# minimal-atmega328p-arduino.net
KiCad netlist of a schematic drawn in EAGLE
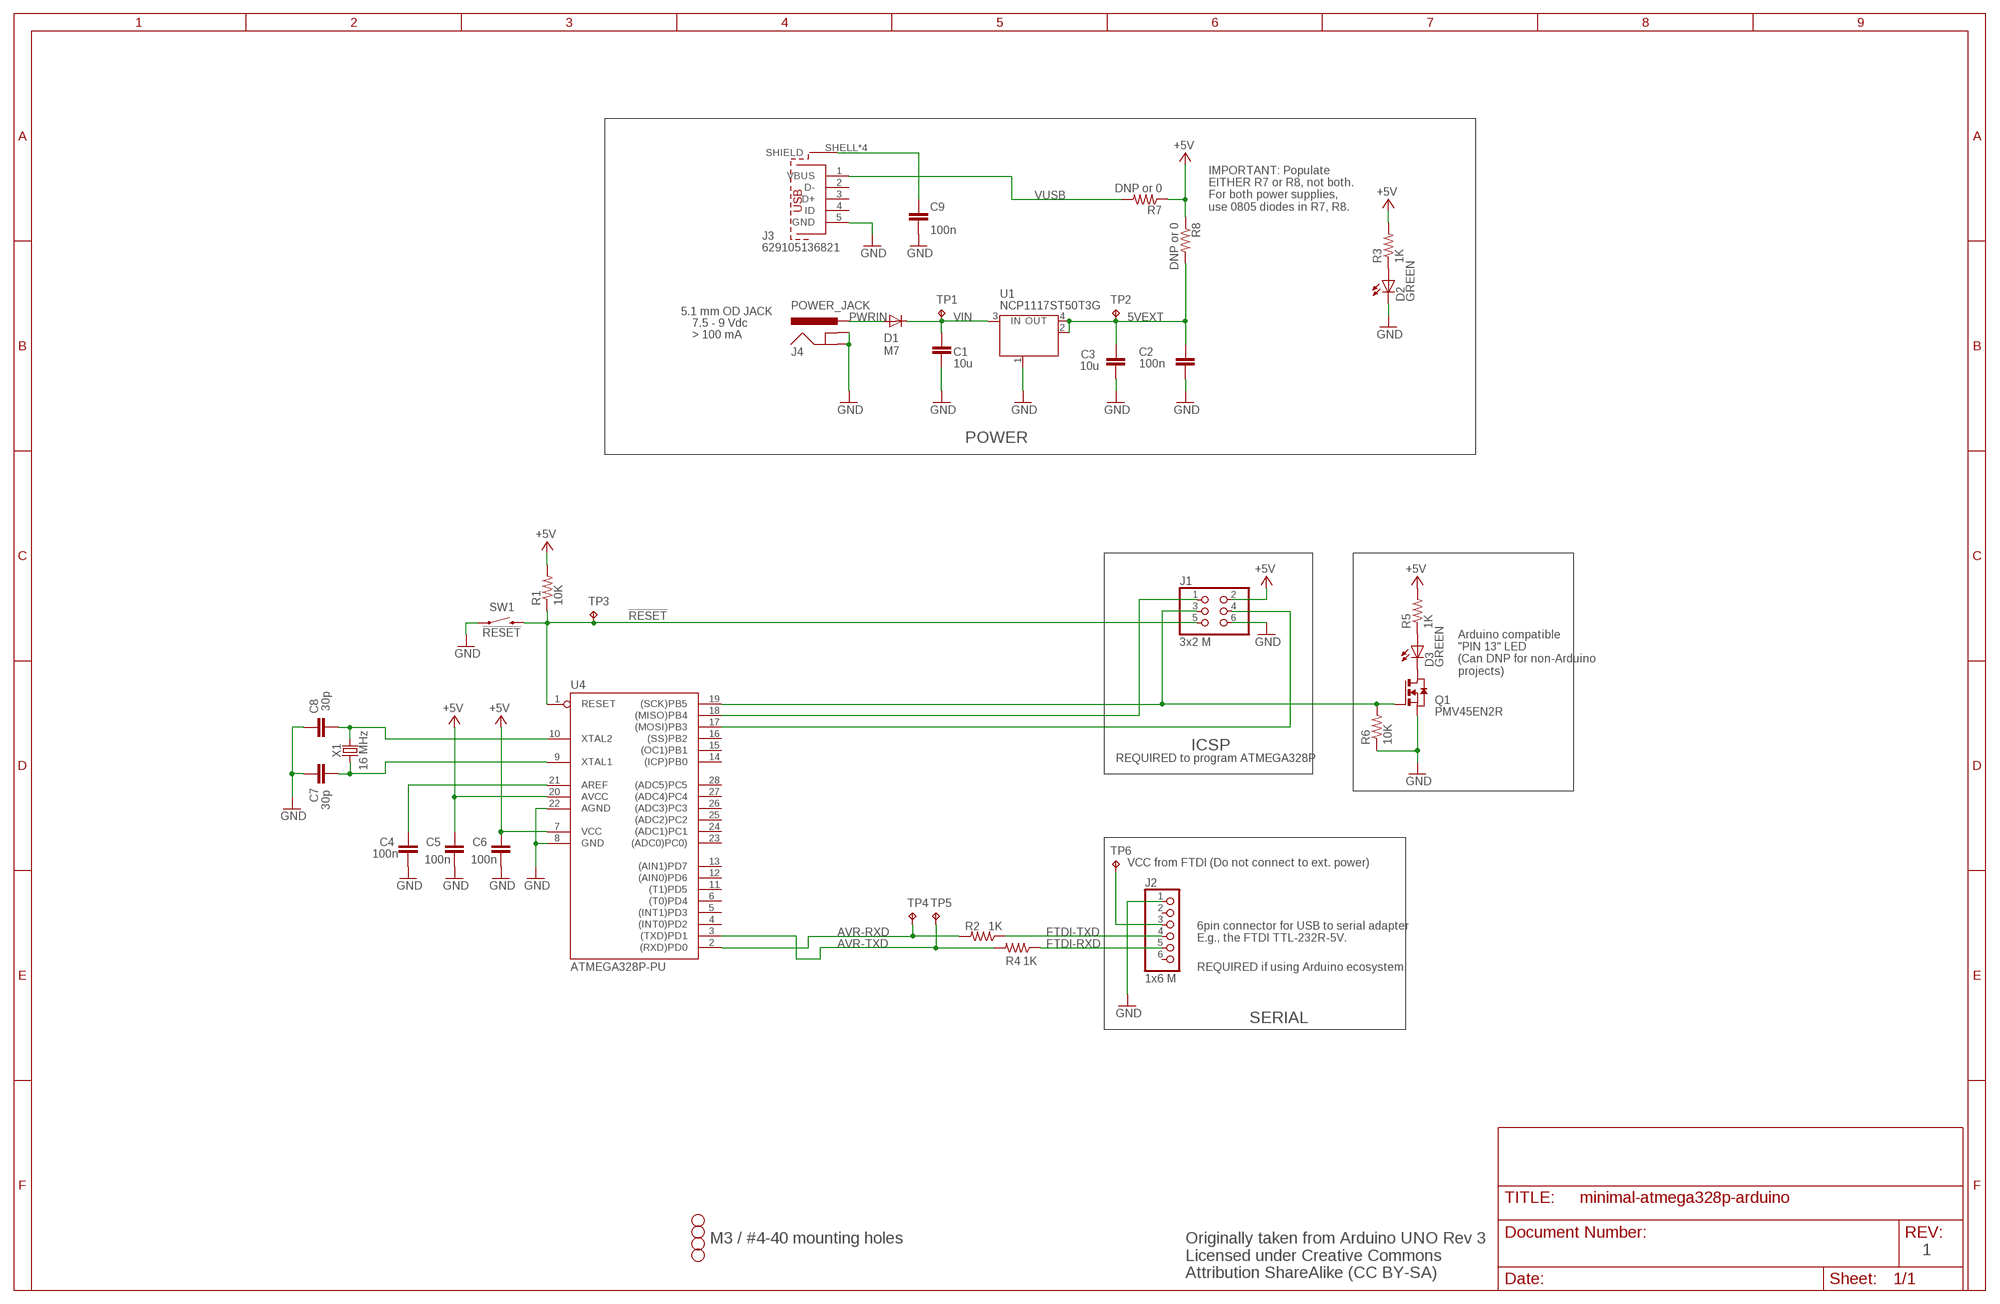
[diagram p0: schematic, sheet 1]

(export (version "E")
  (design (tool "Eeschema 10.0.6"))
  (components
    (comp (ref "C1")
      (value "10u")
      (footprint "eagle-import:C0805K")
      (fields (field (name "MFR") "Samsung") (field (name "MPN") "CL21A106KOQNNNG"))
      (libsource (lib "eagle-import") (part "C-EUC0805K"))
    )
    (comp (ref "C2")
      (value "100n")
      (footprint "eagle-import:C0805K")
      (fields (field (name "MFR") "Samsung") (field (name "MPN") "CL21B104KBCNNNC"))
      (libsource (lib "eagle-import") (part "C-EUC0805K"))
    )
    (comp (ref "C3")
      (value "10u")
      (footprint "eagle-import:C0805K")
      (fields (field (name "MFR") "Samsung") (field (name "MPN") "CL21A106KOQNNNG"))
      (libsource (lib "eagle-import") (part "C-EUC0805K"))
    )
    (comp (ref "C4")
      (value "100n")
      (footprint "eagle-import:C0805K")
      (fields (field (name "MFR") "Samsung") (field (name "MPN") "CL21B104KBCNNNC"))
      (libsource (lib "eagle-import") (part "C-EUC0805K"))
    )
    (comp (ref "C5")
      (value "100n")
      (footprint "eagle-import:C0805K")
      (fields (field (name "MFR") "Samsung") (field (name "MPN") "CL21B104KBCNNNC"))
      (libsource (lib "eagle-import") (part "C-EUC0805K"))
    )
    (comp (ref "C6")
      (value "100n")
      (footprint "eagle-import:C0805K")
      (fields (field (name "MFR") "Samsung") (field (name "MPN") "CL21B104KBCNNNC"))
      (libsource (lib "eagle-import") (part "C-EUC0805K"))
    )
    (comp (ref "C7")
      (value "30p")
      (footprint "eagle-import:C0805K")
      (fields (field (name "MFR") "Samsung") (field (name "MPN") "CL21C180JBANNNC"))
      (libsource (lib "eagle-import") (part "C-EUC0805K"))
    )
    (comp (ref "C8")
      (value "30p")
      (footprint "eagle-import:C0805K")
      (fields (field (name "MFR") "Samsung") (field (name "MPN") "CL21C300JBANNNC"))
      (libsource (lib "eagle-import") (part "C-EUC0805K"))
    )
    (comp (ref "C9")
      (value "100n")
      (footprint "eagle-import:C0805K")
      (fields (field (name "MFR") "Samsung") (field (name "MPN") "CL21B104KBCNNNC"))
      (libsource (lib "eagle-import") (part "C-EUC0805K"))
    )
    (comp (ref "D1")
      (value "M7")
      (footprint "eagle-import:SMB")
      (fields (field (name "MFR") "SMC Diode") (field (name "MPN") "10BQ030TR"))
      (libsource (lib "eagle-import") (part "DIODE-SMB"))
    )
    (comp (ref "D2")
      (value "GREEN")
      (footprint "eagle-import:CHIP-LED0805")
      (fields (field (name "MFR") "Würth Elektronik") (field (name "MPN") "150080GS75000"))
      (libsource (lib "eagle-import") (part "LEDCHIP-LED0805"))
    )
    (comp (ref "D3")
      (value "GREEN")
      (footprint "eagle-import:CHIP-LED0805")
      (fields (field (name "MFR") "Würth Elektronik") (field (name "MPN") "150080GS75000"))
      (libsource (lib "eagle-import") (part "LEDCHIP-LED0805"))
    )
    (comp (ref "H1")
      (value "STAND-OFF")
      (footprint "eagle-import:STAND-OFF")
      (libsource (lib "eagle-import") (part "STAND-OFF"))
    )
    (comp (ref "H2")
      (value "STAND-OFF")
      (footprint "eagle-import:STAND-OFF")
      (libsource (lib "eagle-import") (part "STAND-OFF"))
    )
    (comp (ref "H3")
      (value "STAND-OFF")
      (footprint "eagle-import:STAND-OFF")
      (libsource (lib "eagle-import") (part "STAND-OFF"))
    )
    (comp (ref "H4")
      (value "STAND-OFF")
      (footprint "eagle-import:STAND-OFF")
      (libsource (lib "eagle-import") (part "STAND-OFF"))
    )
    (comp (ref "J1")
      (value "3x2 M")
      (footprint "eagle-import:2X03")
      (fields (field (name "MFR") "Harwin") (field (name "MPN") "M20-9980345"))
      (libsource (lib "eagle-import") (part "PINHD-2X3"))
    )
    (comp (ref "J2")
      (value "1x6 M")
      (footprint "eagle-import:1X06")
      (fields (field (name "MFR") "Sullins") (field (name "MPN") "PRPC006SAAN-RC"))
      (libsource (lib "eagle-import") (part "PINHD-1X6"))
    )
    (comp (ref "J3")
      (value "629105136821")
      (footprint "eagle-import:629105136821")
      (fields (field (name "MFR") "Wurth"))
      (libsource (lib "eagle-import") (part "629105136821"))
    )
    (comp (ref "J4")
      (value "POWER_JACK")
      (footprint "eagle-import:POWER_JACK_PTH")
      (fields (field (name "MFR") "CUI") (field (name "MPN") "PJ-202A"))
      (libsource (lib "eagle-import") (part "POWER_JACK"))
    )
    (comp (ref "Q1")
      (value "PMV45EN2R")
      (footprint "eagle-import:SOT-23")
      (fields (field (name "MFR") "Nexperia") (field (name "MPN") "PMV45EN2R"))
      (libsource (lib "eagle-import") (part "NMOSSOT23"))
    )
    (comp (ref "R1")
      (value "10K")
      (footprint "eagle-import:R0805")
      (fields (field (name "MFR") "Yageo") (field (name "MPN") "RC0805FR-0710KL"))
      (libsource (lib "eagle-import") (part "R-US_R0805"))
    )
    (comp (ref "R2")
      (value "1K")
      (footprint "eagle-import:R0805")
      (fields (field (name "MFR") "Yageo") (field (name "MPN") "RC0805FR-071KL"))
      (libsource (lib "eagle-import") (part "R-US_R0805"))
    )
    (comp (ref "R3")
      (value "1K")
      (footprint "eagle-import:R0805")
      (fields (field (name "MFR") "Yageo") (field (name "MPN") "RC0805FR-071KL"))
      (libsource (lib "eagle-import") (part "R-US_R0805"))
    )
    (comp (ref "R4")
      (value "1K")
      (footprint "eagle-import:R0805")
      (fields (field (name "MFR") "Yageo") (field (name "MPN") "RC0805FR-071KL"))
      (libsource (lib "eagle-import") (part "R-US_R0805"))
    )
    (comp (ref "R5")
      (value "1K")
      (footprint "eagle-import:R0805")
      (fields (field (name "MFR") "Yageo") (field (name "MPN") "RC0805FR-071KL"))
      (libsource (lib "eagle-import") (part "R-US_R0805"))
    )
    (comp (ref "R6")
      (value "10K")
      (footprint "eagle-import:R0805")
      (fields (field (name "MFR") "Yageo") (field (name "MPN") "RC0805FR-0710KL"))
      (libsource (lib "eagle-import") (part "R-US_R0805"))
    )
    (comp (ref "R7")
      (value "DNP or 0")
      (footprint "eagle-import:R0805")
      (fields (field (name "MFR") "Yageo") (field (name "MPN") "RC0805JR-070RL"))
      (libsource (lib "eagle-import") (part "R-US_R0805"))
    )
    (comp (ref "R8")
      (value "DNP or 0")
      (footprint "eagle-import:R0805")
      (fields (field (name "MFR") "Yageo") (field (name "MPN") "RC0805JR-070RL"))
      (libsource (lib "eagle-import") (part "R-US_R0805"))
    )
    (comp (ref "SW1")
      (value "!RESET")
      (footprint "eagle-import:TACTILE_SWITCH_SMD")
      (fields (field (name "MFR") "C&K") (field (name "MPN") "RS-187R05A2-DS MT RT"))
      (libsource (lib "eagle-import") (part "SWITCH-MOMENTARY-2SMD"))
    )
    (comp (ref "TP1")
      (value "TPPAD1-13")
      (footprint "eagle-import:P1-13")
      (libsource (lib "eagle-import") (part "TPPAD1-13"))
    )
    (comp (ref "TP2")
      (value "TPPAD1-13")
      (footprint "eagle-import:P1-13")
      (libsource (lib "eagle-import") (part "TPPAD1-13"))
    )
    (comp (ref "TP3")
      (value "TPPAD1-13")
      (footprint "eagle-import:P1-13")
      (libsource (lib "eagle-import") (part "TPPAD1-13"))
    )
    (comp (ref "TP4")
      (value "TPPAD1-13")
      (footprint "eagle-import:P1-13")
      (libsource (lib "eagle-import") (part "TPPAD1-13"))
    )
    (comp (ref "TP5")
      (value "TPPAD1-13")
      (footprint "eagle-import:P1-13")
      (libsource (lib "eagle-import") (part "TPPAD1-13"))
    )
    (comp (ref "TP6")
      (value "TPPAD1-13")
      (footprint "eagle-import:P1-13")
      (libsource (lib "eagle-import") (part "TPPAD1-13"))
    )
    (comp (ref "U1")
      (value "NCP1117ST50T3G")
      (footprint "eagle-import:SOT223")
      (fields (field (name "MFR") "ON Semiconductor"))
      (libsource (lib "eagle-import") (part "MC33269ST-3.3T3"))
    )
    (comp (ref "U4")
      (value "ATMEGA328P-PU")
      (footprint "eagle-import:DIL28-3")
      (fields (field (name "MFR") "Microchip"))
      (libsource (lib "eagle-import") (part "ATMEGA328P-PU"))
    )
    (comp (ref "X1")
      (value "16 MHz")
      (footprint "eagle-import:HC49UP")
      (fields (field (name "MFR") "ECS") (field (name "MPN") "ECS-160-18-5PX-TR"))
      (libsource (lib "eagle-import") (part "CRYSTALSMD-HC49UP"))
    )
  )
  (nets
    (net (code "1") (name "+5V") (class "Default")
      (node (ref "C5") (pin "2") (pinfunction "2_2") (pintype "passive"))
      (node (ref "C6") (pin "2") (pinfunction "2_2") (pintype "passive"))
      (node (ref "J1") (pin "2") (pinfunction "2_2") (pintype "passive"))
      (node (ref "R1") (pin "2") (pinfunction "2_2") (pintype "passive"))
      (node (ref "R3") (pin "2") (pinfunction "2_2") (pintype "passive"))
      (node (ref "R5") (pin "2") (pinfunction "2_2") (pintype "passive"))
      (node (ref "R7") (pin "1") (pinfunction "1_1") (pintype "passive"))
      (node (ref "R8") (pin "1") (pinfunction "1_1") (pintype "passive"))
      (node (ref "U4") (pin "20") (pinfunction "AVCC_20") (pintype "power_in"))
      (node (ref "U4") (pin "7") (pinfunction "VCC_7") (pintype "power_in"))
    )
    (net (code "2") (name "/5VEXT") (class "Default")
      (node (ref "C2") (pin "2") (pinfunction "2_2") (pintype "passive"))
      (node (ref "C3") (pin "1") (pinfunction "1_1") (pintype "passive"))
      (node (ref "R8") (pin "2") (pinfunction "2_2") (pintype "passive"))
      (node (ref "TP2") (pin "TP") (pinfunction "TP_TP") (pintype "input"))
      (node (ref "U1") (pin "2") (pinfunction "OUT_2") (pintype "passive"))
      (node (ref "U1") (pin "4") (pinfunction "OUT_4") (pintype "passive"))
    )
    (net (code "3") (name "/AVR-RXD") (class "Default")
      (node (ref "R2") (pin "2") (pinfunction "2_2") (pintype "passive"))
      (node (ref "TP4") (pin "TP") (pinfunction "TP_TP") (pintype "input"))
      (node (ref "U4") (pin "2") (pinfunction "(RXD)PD0_2") (pintype "bidirectional"))
    )
    (net (code "4") (name "/AVR-TXD") (class "Default")
      (node (ref "R4") (pin "2") (pinfunction "2_2") (pintype "passive"))
      (node (ref "TP5") (pin "TP") (pinfunction "TP_TP") (pintype "input"))
      (node (ref "U4") (pin "3") (pinfunction "(TXD)PD1_3") (pintype "bidirectional"))
    )
    (net (code "5") (name "/FTDI-RXD") (class "Default")
      (node (ref "J2") (pin "5") (pinfunction "5_5") (pintype "passive"))
      (node (ref "R4") (pin "1") (pinfunction "1_1") (pintype "passive"))
    )
    (net (code "6") (name "/FTDI-TXD") (class "Default")
      (node (ref "J2") (pin "4") (pinfunction "4_4") (pintype "passive"))
      (node (ref "R2") (pin "1") (pinfunction "1_1") (pintype "passive"))
    )
    (net (code "7") (name "/PWRIN") (class "Default")
      (node (ref "D1") (pin "A") (pinfunction "A_A") (pintype "passive"))
      (node (ref "J4") (pin "PWR") (pinfunction "PWR_PWR") (pintype "bidirectional"))
    )
    (net (code "8") (name "/VIN") (class "Default")
      (node (ref "C1") (pin "1") (pinfunction "1_1") (pintype "passive"))
      (node (ref "D1") (pin "C") (pinfunction "C_C") (pintype "passive"))
      (node (ref "TP1") (pin "TP") (pinfunction "TP_TP") (pintype "input"))
      (node (ref "U1") (pin "3") (pinfunction "IN_3") (pintype "input"))
    )
    (net (code "9") (name "/VUSB") (class "Default")
      (node (ref "J3") (pin "1") (pinfunction "VBUS_1") (pintype "passive"))
      (node (ref "R7") (pin "2") (pinfunction "2_2") (pintype "passive"))
    )
    (net (code "10") (name "/~{RESET}") (class "Default")
      (node (ref "J1") (pin "5") (pinfunction "5_5") (pintype "passive"))
      (node (ref "R1") (pin "1") (pinfunction "1_1") (pintype "passive"))
      (node (ref "SW1") (pin "3") (pinfunction "2_3") (pintype "passive"))
      (node (ref "TP3") (pin "TP") (pinfunction "TP_TP") (pintype "input"))
      (node (ref "U4") (pin "1") (pinfunction "RESET_1") (pintype "input"))
    )
    (net (code "11") (name "GND") (class "Default")
      (node (ref "C1") (pin "2") (pinfunction "2_2") (pintype "passive"))
      (node (ref "C2") (pin "1") (pinfunction "1_1") (pintype "passive"))
      (node (ref "C3") (pin "2") (pinfunction "2_2") (pintype "passive"))
      (node (ref "C4") (pin "1") (pinfunction "1_1") (pintype "passive"))
      (node (ref "C5") (pin "1") (pinfunction "1_1") (pintype "passive"))
      (node (ref "C6") (pin "1") (pinfunction "1_1") (pintype "passive"))
      (node (ref "C7") (pin "2") (pinfunction "2_2") (pintype "passive"))
      (node (ref "C8") (pin "2") (pinfunction "2_2") (pintype "passive"))
      (node (ref "C9") (pin "1") (pinfunction "1_1") (pintype "passive"))
      (node (ref "D2") (pin "C") (pinfunction "C_C") (pintype "passive"))
      (node (ref "J1") (pin "6") (pinfunction "6_6") (pintype "passive"))
      (node (ref "J2") (pin "1") (pinfunction "1_1") (pintype "passive"))
      (node (ref "J3") (pin "5") (pinfunction "GND_5") (pintype "passive"))
      (node (ref "J4") (pin "GND") (pinfunction "GND_GND") (pintype "bidirectional"))
      (node (ref "J4") (pin "GNDBREAK") (pinfunction "GNDBREAK_GNDBREAK") (pintype "bidirectional"))
      (node (ref "Q1") (pin "2") (pinfunction "S_2") (pintype "passive"))
      (node (ref "R6") (pin "1") (pinfunction "1_1") (pintype "passive"))
      (node (ref "SW1") (pin "1") (pinfunction "1_1") (pintype "passive"))
      (node (ref "U1") (pin "1") (pinfunction "GND/ADJ_1") (pintype "input"))
      (node (ref "U4") (pin "22") (pinfunction "AGND_22") (pintype "power_in"))
      (node (ref "U4") (pin "8") (pinfunction "GND_8") (pintype "power_in"))
    )
    (net (code "12") (name "Net-(C9-Pad2)") (class "Default")
      (node (ref "C9") (pin "2") (pinfunction "2_2") (pintype "passive"))
      (node (ref "J3") (pin "SHELL") (pinfunction "SHIELD_SHELL") (pintype "passive"))
      (node (ref "J3") (pin "SHELL1") (pinfunction "SHIELD_SHELL1") (pintype "passive"))
      (node (ref "J3") (pin "SHELL2") (pinfunction "SHIELD_SHELL2") (pintype "passive"))
      (node (ref "J3") (pin "SHELL3") (pinfunction "SHIELD_SHELL3") (pintype "passive"))
    )
    (net (code "13") (name "Net-(D2-PadA)") (class "Default")
      (node (ref "D2") (pin "A") (pinfunction "A_A") (pintype "passive"))
      (node (ref "R3") (pin "1") (pinfunction "1_1") (pintype "passive"))
    )
    (net (code "14") (name "Net-(D3-PadA)") (class "Default")
      (node (ref "D3") (pin "A") (pinfunction "A_A") (pintype "passive"))
      (node (ref "R5") (pin "1") (pinfunction "1_1") (pintype "passive"))
    )
    (net (code "15") (name "Net-(J2-Pad3)") (class "Default")
      (node (ref "J2") (pin "3") (pinfunction "3_3") (pintype "passive"))
      (node (ref "TP6") (pin "TP") (pinfunction "TP_TP") (pintype "input"))
    )
    (net (code "16") (name "Net-(Q1-D)") (class "Default")
      (node (ref "D3") (pin "C") (pinfunction "C_C") (pintype "passive"))
      (node (ref "Q1") (pin "1") (pinfunction "D_1") (pintype "passive"))
    )
    (net (code "17") (name "Net-(Q1-G)") (class "Default")
      (node (ref "J1") (pin "3") (pinfunction "3_3") (pintype "passive"))
      (node (ref "Q1") (pin "3") (pinfunction "G_3") (pintype "passive"))
      (node (ref "R6") (pin "2") (pinfunction "2_2") (pintype "passive"))
      (node (ref "U4") (pin "19") (pinfunction "(SCK)PB5_19") (pintype "bidirectional"))
    )
    (net (code "18") (name "Net-(U4-(MISO)PB4)") (class "Default")
      (node (ref "J1") (pin "1") (pinfunction "1_1") (pintype "passive"))
      (node (ref "U4") (pin "18") (pinfunction "(MISO)PB4_18") (pintype "bidirectional"))
    )
    (net (code "19") (name "Net-(U4-(MOSI)PB3)") (class "Default")
      (node (ref "J1") (pin "4") (pinfunction "4_4") (pintype "passive"))
      (node (ref "U4") (pin "17") (pinfunction "(MOSI)PB3_17") (pintype "bidirectional"))
    )
    (net (code "20") (name "Net-(U4-AREF)") (class "Default")
      (node (ref "C4") (pin "2") (pinfunction "2_2") (pintype "passive"))
      (node (ref "U4") (pin "21") (pinfunction "AREF_21") (pintype "passive"))
    )
    (net (code "21") (name "Net-(U4-XTAL1)") (class "Default")
      (node (ref "C7") (pin "1") (pinfunction "1_1") (pintype "passive"))
      (node (ref "U4") (pin "9") (pinfunction "XTAL1_9") (pintype "bidirectional"))
      (node (ref "X1") (pin "1") (pinfunction "1_1") (pintype "passive"))
    )
    (net (code "22") (name "Net-(U4-XTAL2)") (class "Default")
      (node (ref "C8") (pin "1") (pinfunction "1_1") (pintype "passive"))
      (node (ref "U4") (pin "10") (pinfunction "XTAL2_10") (pintype "bidirectional"))
      (node (ref "X1") (pin "2") (pinfunction "2_2") (pintype "passive"))
    )
    (net (code "23") (name "unconnected-(J2-Pad2)") (class "Default")
      (node (ref "J2") (pin "2") (pinfunction "2_2") (pintype "passive"))
    )
    (net (code "24") (name "unconnected-(J2-Pad6)") (class "Default")
      (node (ref "J2") (pin "6") (pinfunction "6_6") (pintype "passive"))
    )
    (net (code "25") (name "unconnected-(J3-D+-Pad3)") (class "Default")
      (node (ref "J3") (pin "3") (pinfunction "D+_3") (pintype "passive"))
    )
    (net (code "26") (name "unconnected-(J3-D--Pad2)") (class "Default")
      (node (ref "J3") (pin "2") (pinfunction "D-_2") (pintype "passive"))
    )
    (net (code "27") (name "unconnected-(J3-ID-Pad4)") (class "Default")
      (node (ref "J3") (pin "4") (pinfunction "ID_4") (pintype "passive"))
    )
    (net (code "28") (name "unconnected-(U4-(ADC0)PC0)-Pad23)") (class "Default")
      (node (ref "U4") (pin "23") (pinfunction "(ADC0)PC0)_23") (pintype "bidirectional"))
    )
    (net (code "29") (name "unconnected-(U4-(ADC1)PC1-Pad24)") (class "Default")
      (node (ref "U4") (pin "24") (pinfunction "(ADC1)PC1_24") (pintype "bidirectional"))
    )
    (net (code "30") (name "unconnected-(U4-(ADC2)PC2-Pad25)") (class "Default")
      (node (ref "U4") (pin "25") (pinfunction "(ADC2)PC2_25") (pintype "bidirectional"))
    )
    (net (code "31") (name "unconnected-(U4-(ADC3)PC3-Pad26)") (class "Default")
      (node (ref "U4") (pin "26") (pinfunction "(ADC3)PC3_26") (pintype "bidirectional"))
    )
    (net (code "32") (name "unconnected-(U4-(ADC4)PC4-Pad27)") (class "Default")
      (node (ref "U4") (pin "27") (pinfunction "(ADC4)PC4_27") (pintype "bidirectional"))
    )
    (net (code "33") (name "unconnected-(U4-(ADC5)PC5-Pad28)") (class "Default")
      (node (ref "U4") (pin "28") (pinfunction "(ADC5)PC5_28") (pintype "bidirectional"))
    )
    (net (code "34") (name "unconnected-(U4-(AIN0)PD6-Pad12)") (class "Default")
      (node (ref "U4") (pin "12") (pinfunction "(AIN0)PD6_12") (pintype "bidirectional"))
    )
    (net (code "35") (name "unconnected-(U4-(AIN1)PD7-Pad13)") (class "Default")
      (node (ref "U4") (pin "13") (pinfunction "(AIN1)PD7_13") (pintype "bidirectional"))
    )
    (net (code "36") (name "unconnected-(U4-(ICP)PB0-Pad14)") (class "Default")
      (node (ref "U4") (pin "14") (pinfunction "(ICP)PB0_14") (pintype "bidirectional"))
    )
    (net (code "37") (name "unconnected-(U4-(INT0)PD2-Pad4)") (class "Default")
      (node (ref "U4") (pin "4") (pinfunction "(INT0)PD2_4") (pintype "bidirectional"))
    )
    (net (code "38") (name "unconnected-(U4-(INT1)PD3-Pad5)") (class "Default")
      (node (ref "U4") (pin "5") (pinfunction "(INT1)PD3_5") (pintype "bidirectional"))
    )
    (net (code "39") (name "unconnected-(U4-(OC1)PB1-Pad15)") (class "Default")
      (node (ref "U4") (pin "15") (pinfunction "(OC1)PB1_15") (pintype "bidirectional"))
    )
    (net (code "40") (name "unconnected-(U4-(SS)PB2-Pad16)") (class "Default")
      (node (ref "U4") (pin "16") (pinfunction "(SS)PB2_16") (pintype "bidirectional"))
    )
    (net (code "41") (name "unconnected-(U4-(T0)PD4-Pad6)") (class "Default")
      (node (ref "U4") (pin "6") (pinfunction "(T0)PD4_6") (pintype "bidirectional"))
    )
    (net (code "42") (name "unconnected-(U4-(T1)PD5-Pad11)") (class "Default")
      (node (ref "U4") (pin "11") (pinfunction "(T1)PD5_11") (pintype "bidirectional"))
    )
  )
)
